# Sidekick_Breakout_V1_0.net
KiCad netlist of a schematic drawn in EasyEDA
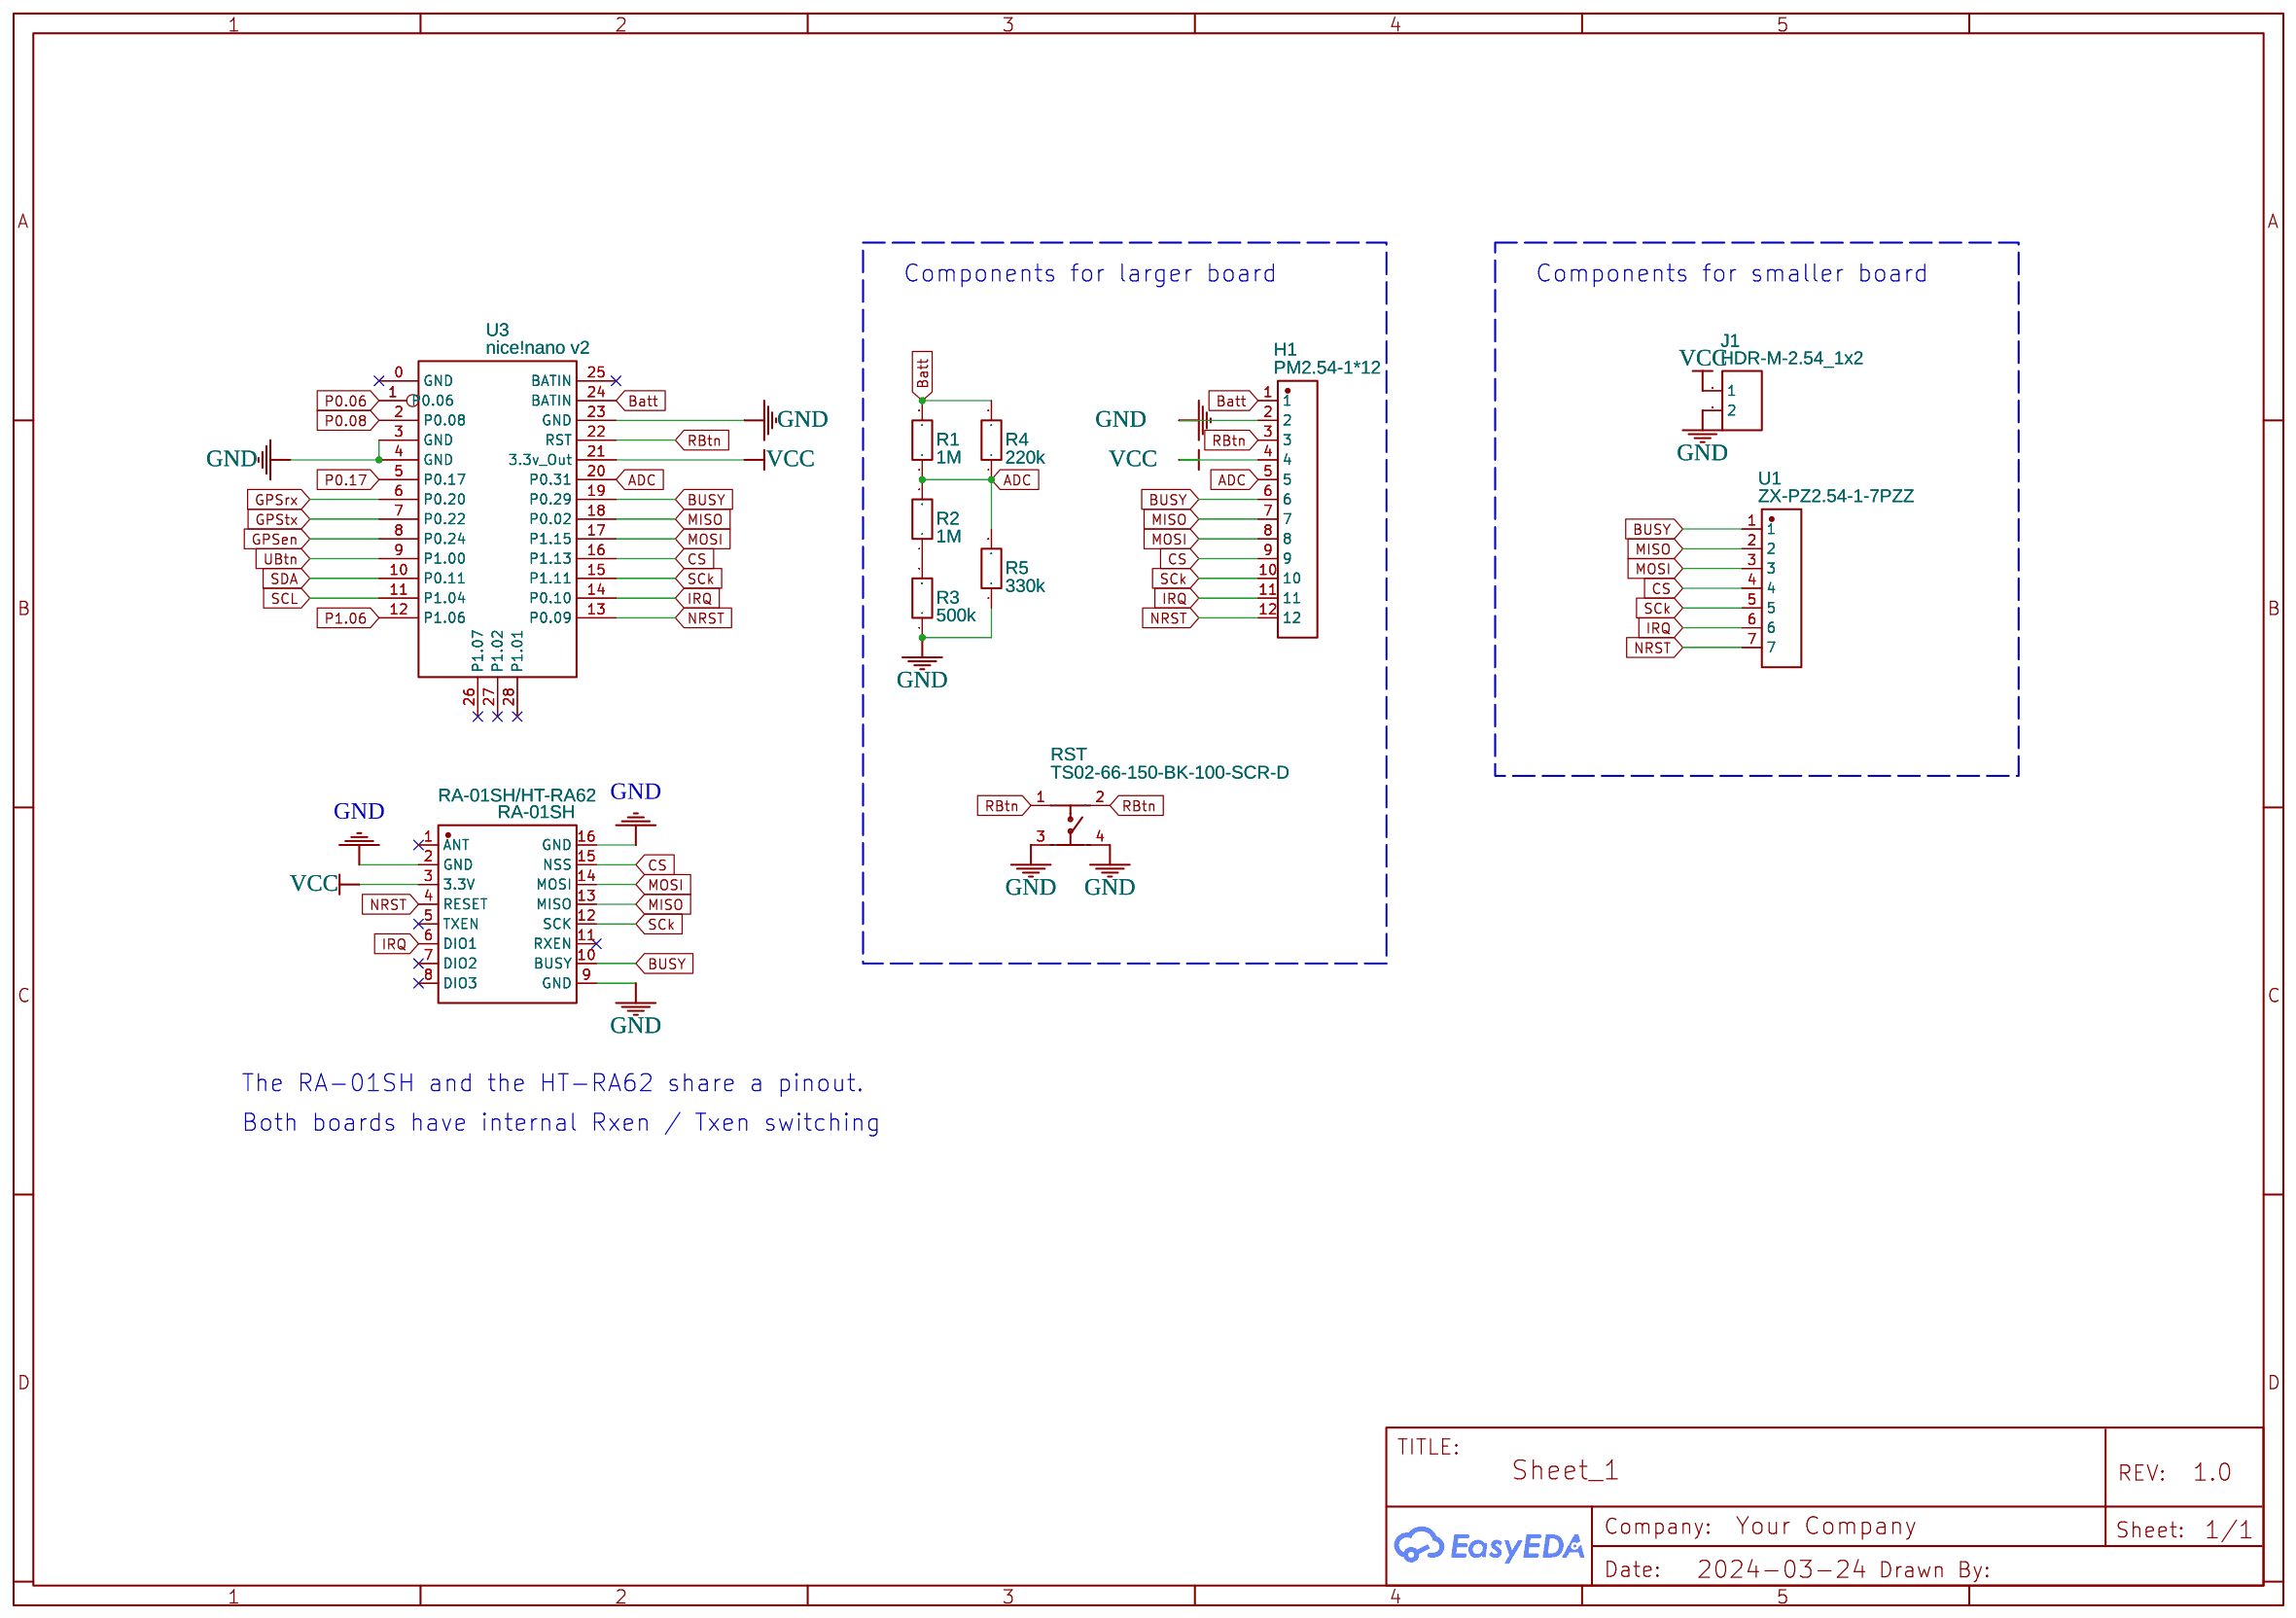
[diagram p0: schematic sheet]

(export (version "E")
  (design (tool "Eeschema 10.0.6"))
  (components
    (comp (ref "H1")
      (value "PM2.54-1*12")
      (fields (field (name "Manufacturer") "ZHOURI(洲日)"))
      (libsource (lib "") (part "PM2.54-1*12"))
    )
    (comp (ref "J1") (value "HDR-M-2.54_1x2") (libsource (lib "") (part "HDR-M-2.54_1x2")))
    (comp (ref "R1") (value "1M") (libsource (lib "") (part "R_1206_EU")))
    (comp (ref "R2") (value "1M") (libsource (lib "") (part "R_1206_EU")))
    (comp (ref "R3") (value "500k") (libsource (lib "") (part "R_1206_EU")))
    (comp (ref "R4") (value "220k") (libsource (lib "") (part "R_AXIAL-0.3_EU")))
    (comp (ref "R5") (value "330k") (libsource (lib "") (part "R_AXIAL-0.3_EU")))
    (comp (ref "RA-01SH/HT-RA62")
      (value "RA-01SH")
      (fields (field (name "Manufacturer Part") "Ra-01SH") (field (name "Manufacturer") "Ai-Thinker(安信可)"))
      (libsource (lib "") (part "RA-01SH"))
    )
    (comp (ref "RST")
      (value "TS02-66-150-BK-100-SCR-D")
      (fields (field (name "Manufacturer") "CUI"))
      (libsource (lib "") (part "TS02-66-150-BK-100-SCR-D"))
    )
    (comp (ref "U1")
      (value "ZX-PZ2.54-1-7PZZ")
      (fields (field (name "Manufacturer") "Megastar(兆星)"))
      (libsource (lib "") (part "ZX-PZ2.54-1-7PZZ"))
    )
    (comp (ref "U3")
      (value "nice!nano v2")
      (fields (field (name "Manufacturer") "nice!"))
      (libsource (lib "") (part "nice!nano v2"))
    )
  )
  (nets
    (net (code "1") (name "ADC") (class "Default")
      (node (ref "H1") (pin "5") (pinfunction "5_5") (pintype "unspecified"))
      (node (ref "R1") (pin "1") (pinfunction "1_1") (pintype "unspecified"))
      (node (ref "R2") (pin "2") (pinfunction "2_2") (pintype "unspecified"))
      (node (ref "R4") (pin "1") (pinfunction "1_1") (pintype "unspecified"))
      (node (ref "R5") (pin "2") (pinfunction "2_2") (pintype "unspecified"))
      (node (ref "U3") (pin "20") (pinfunction "P0.31_20") (pintype "bidirectional"))
    )
    (net (code "2") (name "BUSY") (class "Default")
      (node (ref "H1") (pin "6") (pinfunction "6_6") (pintype "unspecified"))
      (node (ref "RA-01SH/HT-RA62") (pin "10") (pinfunction "BUSY_10") (pintype "unspecified"))
      (node (ref "U1") (pin "1") (pinfunction "1_1") (pintype "unspecified"))
      (node (ref "U3") (pin "19") (pinfunction "P0.29_19") (pintype "bidirectional"))
    )
    (net (code "3") (name "Batt") (class "Default")
      (node (ref "H1") (pin "1") (pinfunction "1_1") (pintype "unspecified"))
      (node (ref "R1") (pin "2") (pinfunction "2_2") (pintype "unspecified"))
      (node (ref "R4") (pin "2") (pinfunction "2_2") (pintype "unspecified"))
      (node (ref "U3") (pin "24") (pinfunction "BATIN_24") (pintype "bidirectional"))
    )
    (net (code "4") (name "CS") (class "Default")
      (node (ref "H1") (pin "9") (pinfunction "9_9") (pintype "unspecified"))
      (node (ref "RA-01SH/HT-RA62") (pin "15") (pinfunction "NSS_15") (pintype "unspecified"))
      (node (ref "U1") (pin "4") (pinfunction "4_4") (pintype "unspecified"))
      (node (ref "U3") (pin "16") (pinfunction "P1.13_16") (pintype "bidirectional"))
    )
    (net (code "5") (name "GND") (class "Default")
      (node (ref "H1") (pin "2") (pinfunction "2_2") (pintype "unspecified"))
      (node (ref "J1") (pin "2") (pinfunction "2_2") (pintype "unspecified"))
      (node (ref "R3") (pin "1") (pinfunction "1_1") (pintype "unspecified"))
      (node (ref "R5") (pin "1") (pinfunction "1_1") (pintype "unspecified"))
      (node (ref "RA-01SH/HT-RA62") (pin "16") (pinfunction "GND_16") (pintype "unspecified"))
      (node (ref "RA-01SH/HT-RA62") (pin "2") (pinfunction "GND_2") (pintype "unspecified"))
      (node (ref "RA-01SH/HT-RA62") (pin "9") (pinfunction "GND_9") (pintype "unspecified"))
      (node (ref "RST") (pin "3") (pinfunction "3_3") (pintype "unspecified"))
      (node (ref "RST") (pin "4") (pinfunction "4_4") (pintype "unspecified"))
      (node (ref "U3") (pin "23") (pinfunction "GND_23") (pintype "bidirectional"))
      (node (ref "U3") (pin "3") (pinfunction "GND_3") (pintype "unspecified"))
      (node (ref "U3") (pin "4") (pinfunction "GND_4") (pintype "unspecified"))
    )
    (net (code "6") (name "GPSen") (class "Default")
      (node (ref "U3") (pin "8") (pinfunction "P0.24_8") (pintype "unspecified"))
    )
    (net (code "7") (name "GPSrx") (class "Default")
      (node (ref "U3") (pin "6") (pinfunction "P0.20_6") (pintype "unspecified"))
    )
    (net (code "8") (name "GPStx") (class "Default")
      (node (ref "U3") (pin "7") (pinfunction "P0.22_7") (pintype "unspecified"))
    )
    (net (code "9") (name "IRQ") (class "Default")
      (node (ref "H1") (pin "11") (pinfunction "11_11") (pintype "unspecified"))
      (node (ref "RA-01SH/HT-RA62") (pin "6") (pinfunction "DIO1_6") (pintype "unspecified"))
      (node (ref "U1") (pin "6") (pinfunction "6_6") (pintype "unspecified"))
      (node (ref "U3") (pin "14") (pinfunction "P0.10_14") (pintype "bidirectional"))
    )
    (net (code "10") (name "MISO") (class "Default")
      (node (ref "H1") (pin "7") (pinfunction "7_7") (pintype "unspecified"))
      (node (ref "RA-01SH/HT-RA62") (pin "13") (pinfunction "MISO_13") (pintype "unspecified"))
      (node (ref "U1") (pin "2") (pinfunction "2_2") (pintype "unspecified"))
      (node (ref "U3") (pin "18") (pinfunction "P0.02_18") (pintype "bidirectional"))
    )
    (net (code "11") (name "MOSI") (class "Default")
      (node (ref "H1") (pin "8") (pinfunction "8_8") (pintype "unspecified"))
      (node (ref "RA-01SH/HT-RA62") (pin "14") (pinfunction "MOSI_14") (pintype "unspecified"))
      (node (ref "U1") (pin "3") (pinfunction "3_3") (pintype "unspecified"))
      (node (ref "U3") (pin "17") (pinfunction "P1.15_17") (pintype "bidirectional"))
    )
    (net (code "12") (name "NRST") (class "Default")
      (node (ref "H1") (pin "12") (pinfunction "12_12") (pintype "unspecified"))
      (node (ref "RA-01SH/HT-RA62") (pin "4") (pinfunction "RESET_4") (pintype "unspecified"))
      (node (ref "U1") (pin "7") (pinfunction "7_7") (pintype "unspecified"))
      (node (ref "U3") (pin "13") (pinfunction "P0.09_13") (pintype "bidirectional"))
    )
    (net (code "13") (name "Net-(R2-Pad1)") (class "Default")
      (node (ref "R2") (pin "1") (pinfunction "1_1") (pintype "unspecified"))
      (node (ref "R3") (pin "2") (pinfunction "2_2") (pintype "unspecified"))
    )
    (net (code "14") (name "P0.06") (class "Default")
      (node (ref "U3") (pin "1") (pinfunction "P0.06_1") (pintype "input"))
    )
    (net (code "15") (name "P0.08") (class "Default")
      (node (ref "U3") (pin "2") (pinfunction "P0.08_2") (pintype "input"))
    )
    (net (code "16") (name "P0.17") (class "Default")
      (node (ref "U3") (pin "5") (pinfunction "P0.17_5") (pintype "unspecified"))
    )
    (net (code "17") (name "P1.06") (class "Default")
      (node (ref "U3") (pin "12") (pinfunction "P1.06_12") (pintype "unspecified"))
    )
    (net (code "18") (name "RBtn") (class "Default")
      (node (ref "H1") (pin "3") (pinfunction "3_3") (pintype "unspecified"))
      (node (ref "RST") (pin "1") (pinfunction "1_1") (pintype "unspecified"))
      (node (ref "RST") (pin "2") (pinfunction "2_2") (pintype "unspecified"))
      (node (ref "U3") (pin "22") (pinfunction "RST_22") (pintype "bidirectional"))
    )
    (net (code "19") (name "SCL") (class "Default")
      (node (ref "U3") (pin "11") (pinfunction "P1.04_11") (pintype "unspecified"))
    )
    (net (code "20") (name "SCk") (class "Default")
      (node (ref "H1") (pin "10") (pinfunction "10_10") (pintype "unspecified"))
      (node (ref "RA-01SH/HT-RA62") (pin "12") (pinfunction "SCK_12") (pintype "unspecified"))
      (node (ref "U1") (pin "5") (pinfunction "5_5") (pintype "unspecified"))
      (node (ref "U3") (pin "15") (pinfunction "P1.11_15") (pintype "bidirectional"))
    )
    (net (code "21") (name "SDA") (class "Default")
      (node (ref "U3") (pin "10") (pinfunction "P0.11_10") (pintype "unspecified"))
    )
    (net (code "22") (name "UBtn") (class "Default")
      (node (ref "U3") (pin "9") (pinfunction "P1.00_9") (pintype "unspecified"))
    )
    (net (code "23") (name "VCC") (class "Default")
      (node (ref "H1") (pin "4") (pinfunction "4_4") (pintype "unspecified"))
      (node (ref "J1") (pin "1") (pinfunction "1_1") (pintype "unspecified"))
      (node (ref "RA-01SH/HT-RA62") (pin "3") (pinfunction "3.3V_3") (pintype "unspecified"))
      (node (ref "U3") (pin "21") (pinfunction "3.3v_Out_21") (pintype "bidirectional"))
    )
    (net (code "24") (name "unconnected-(RA-01SH/HT-RA62-ANT-Pad1)") (class "Default")
      (node (ref "RA-01SH/HT-RA62") (pin "1") (pinfunction "ANT_1") (pintype "unspecified+no_connect"))
    )
    (net (code "25") (name "unconnected-(RA-01SH/HT-RA62-DIO2-Pad7)") (class "Default")
      (node (ref "RA-01SH/HT-RA62") (pin "7") (pinfunction "DIO2_7") (pintype "unspecified+no_connect"))
    )
    (net (code "26") (name "unconnected-(RA-01SH/HT-RA62-DIO3-Pad8)") (class "Default")
      (node (ref "RA-01SH/HT-RA62") (pin "8") (pinfunction "DIO3_8") (pintype "unspecified+no_connect"))
    )
    (net (code "27") (name "unconnected-(RA-01SH/HT-RA62-RXEN-Pad11)") (class "Default")
      (node (ref "RA-01SH/HT-RA62") (pin "11") (pinfunction "RXEN_11") (pintype "unspecified+no_connect"))
    )
    (net (code "28") (name "unconnected-(RA-01SH/HT-RA62-TXEN-Pad5)") (class "Default")
      (node (ref "RA-01SH/HT-RA62") (pin "5") (pinfunction "TXEN_5") (pintype "unspecified+no_connect"))
    )
    (net (code "29") (name "unconnected-(U3-BATIN-Pad25)") (class "Default")
      (node (ref "U3") (pin "25") (pinfunction "BATIN_25") (pintype "bidirectional+no_connect"))
    )
    (net (code "30") (name "unconnected-(U3-GND-Pad0)") (class "Default")
      (node (ref "U3") (pin "0") (pinfunction "GND_0") (pintype "unspecified+no_connect"))
    )
    (net (code "31") (name "unconnected-(U3-P1.01-Pad28)") (class "Default")
      (node (ref "U3") (pin "28") (pinfunction "P1.01_28") (pintype "unspecified+no_connect"))
    )
    (net (code "32") (name "unconnected-(U3-P1.02-Pad27)") (class "Default")
      (node (ref "U3") (pin "27") (pinfunction "P1.02_27") (pintype "unspecified+no_connect"))
    )
    (net (code "33") (name "unconnected-(U3-P1.07-Pad26)") (class "Default")
      (node (ref "U3") (pin "26") (pinfunction "P1.07_26") (pintype "unspecified+no_connect"))
    )
  )
)
